# Vibrationdriver_WS2811.net
KiCad netlist of a schematic drawn in EAGLE
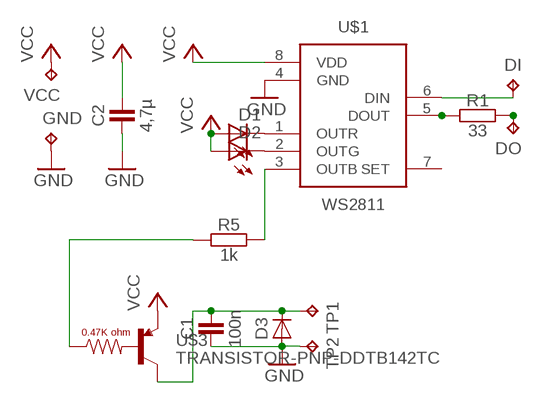
[diagram p0: schematic, sheet 1]

(export (version "E")
  (design (tool "Eeschema 10.0.6"))
  (components
    (comp (ref "C1")
      (value "100n")
      (footprint "eagle-import:C0603")
      (libsource (lib "eagle-import") (part "CAPACITOR-0603"))
    )
    (comp (ref "C2")
      (value "4,7µ")
      (footprint "eagle-import:C0603")
      (libsource (lib "eagle-import") (part "CAPACITOR-0603"))
    )
    (comp (ref "D1")
      (value "LED-0603")
      (footprint "eagle-import:C0603")
      (libsource (lib "eagle-import") (part "LED-0603"))
    )
    (comp (ref "D2")
      (value "LED-0603")
      (footprint "eagle-import:C0603")
      (libsource (lib "eagle-import") (part "LED-0603"))
    )
    (comp (ref "D3")
      (value "DIODE-SOD110")
      (footprint "eagle-import:SOD110")
      (libsource (lib "eagle-import") (part "DIODE-SOD110"))
    )
    (comp (ref "DI")
      (value "TPTP08SQ")
      (footprint "eagle-import:TP08SQ")
      (libsource (lib "eagle-import") (part "TPTP08SQ"))
    )
    (comp (ref "DO")
      (value "TPTP08SQ")
      (footprint "eagle-import:TP08SQ")
      (libsource (lib "eagle-import") (part "TPTP08SQ"))
    )
    (comp (ref "GND")
      (value "TPTP08SQ")
      (footprint "eagle-import:TP08SQ")
      (libsource (lib "eagle-import") (part "TPTP08SQ"))
    )
    (comp (ref "R1")
      (value "33")
      (footprint "eagle-import:C0603")
      (libsource (lib "eagle-import") (part "RESISTOR-0603"))
    )
    (comp (ref "R5")
      (value "1k")
      (footprint "eagle-import:C0603")
      (libsource (lib "eagle-import") (part "RESISTOR-0603"))
    )
    (comp (ref "TP1")
      (value "TPTP20R")
      (footprint "eagle-import:TP20R")
      (libsource (lib "eagle-import") (part "TPTP20R"))
    )
    (comp (ref "TP2")
      (value "TPTP20R")
      (footprint "eagle-import:TP20R")
      (libsource (lib "eagle-import") (part "TPTP20R"))
    )
    (comp (ref "U$1")
      (value "WS2811")
      (footprint "eagle-import:SOP-8")
      (libsource (lib "eagle-import") (part "WS2811"))
    )
    (comp (ref "U$3")
      (value "TRANSISTOR-PNP-DDTB142TC")
      (footprint "eagle-import:SOT23-3")
      (libsource (lib "eagle-import") (part "TRANSISTOR-PNP-DDTB142TC"))
    )
    (comp (ref "VCC")
      (value "TPTP08SQ")
      (footprint "eagle-import:TP08SQ")
      (libsource (lib "eagle-import") (part "TPTP08SQ"))
    )
  )
  (nets
    (net (code "1") (name "GND") (class "Default")
      (node (ref "C1") (pin "1") (pinfunction "1_1") (pintype "passive"))
      (node (ref "C2") (pin "1") (pinfunction "1_1") (pintype "passive"))
      (node (ref "D3") (pin "A") (pinfunction "A_A") (pintype "passive"))
      (node (ref "GND") (pin "TP") (pinfunction "TP_TP") (pintype "input"))
      (node (ref "TP2") (pin "TP") (pinfunction "TP_TP") (pintype "input"))
      (node (ref "U$1") (pin "4") (pinfunction "GND_4") (pintype "bidirectional"))
    )
    (net (code "2") (name "Net-(DO-PadTP)") (class "Default")
      (node (ref "DO") (pin "TP") (pinfunction "TP_TP") (pintype "input"))
      (node (ref "R1") (pin "2") (pinfunction "2_2") (pintype "passive"))
    )
    (net (code "3") (name "Net-(U$1-DIN)") (class "Default")
      (node (ref "DI") (pin "TP") (pinfunction "TP_TP") (pintype "input"))
      (node (ref "U$1") (pin "6") (pinfunction "DIN_6") (pintype "bidirectional"))
    )
    (net (code "4") (name "Net-(U$1-DOUT)") (class "Default")
      (node (ref "R1") (pin "1") (pinfunction "1_1") (pintype "passive"))
      (node (ref "U$1") (pin "5") (pinfunction "DOUT_5") (pintype "bidirectional"))
    )
    (net (code "5") (name "Net-(U$1-OUTB)") (class "Default")
      (node (ref "R5") (pin "2") (pinfunction "2_2") (pintype "passive"))
      (node (ref "U$1") (pin "3") (pinfunction "OUTB_3") (pintype "bidirectional"))
    )
    (net (code "6") (name "Net-(U$1-OUTG)") (class "Default")
      (node (ref "D2") (pin "C") (pinfunction "C_C") (pintype "passive"))
      (node (ref "U$1") (pin "2") (pinfunction "OUTG_2") (pintype "bidirectional"))
    )
    (net (code "7") (name "Net-(U$1-OUTR)") (class "Default")
      (node (ref "D1") (pin "C") (pinfunction "C_C") (pintype "passive"))
      (node (ref "U$1") (pin "1") (pinfunction "OUTR_1") (pintype "bidirectional"))
    )
    (net (code "8") (name "Net-(U$3-B)") (class "Default")
      (node (ref "R5") (pin "1") (pinfunction "1_1") (pintype "passive"))
      (node (ref "U$3") (pin "1") (pinfunction "B_1") (pintype "passive"))
    )
    (net (code "9") (name "Net-(U$3-C)") (class "Default")
      (node (ref "C1") (pin "2") (pinfunction "2_2") (pintype "passive"))
      (node (ref "D3") (pin "C") (pinfunction "C_C") (pintype "passive"))
      (node (ref "TP1") (pin "TP") (pinfunction "TP_TP") (pintype "input"))
      (node (ref "U$3") (pin "3") (pinfunction "C_3") (pintype "passive"))
    )
    (net (code "10") (name "VCC") (class "Default")
      (node (ref "C2") (pin "2") (pinfunction "2_2") (pintype "passive"))
      (node (ref "D1") (pin "A") (pinfunction "A_A") (pintype "passive"))
      (node (ref "D2") (pin "A") (pinfunction "A_A") (pintype "passive"))
      (node (ref "U$1") (pin "8") (pinfunction "VDD_8") (pintype "bidirectional"))
      (node (ref "U$3") (pin "2") (pinfunction "E_2") (pintype "passive"))
      (node (ref "VCC") (pin "TP") (pinfunction "TP_TP") (pintype "input"))
    )
    (net (code "11") (name "unconnected-(U$1-SET-Pad7)") (class "Default")
      (node (ref "U$1") (pin "7") (pinfunction "SET_7") (pintype "bidirectional"))
    )
  )
)
